# HCM6352_v10.net
KiCad netlist of a schematic drawn in EAGLE
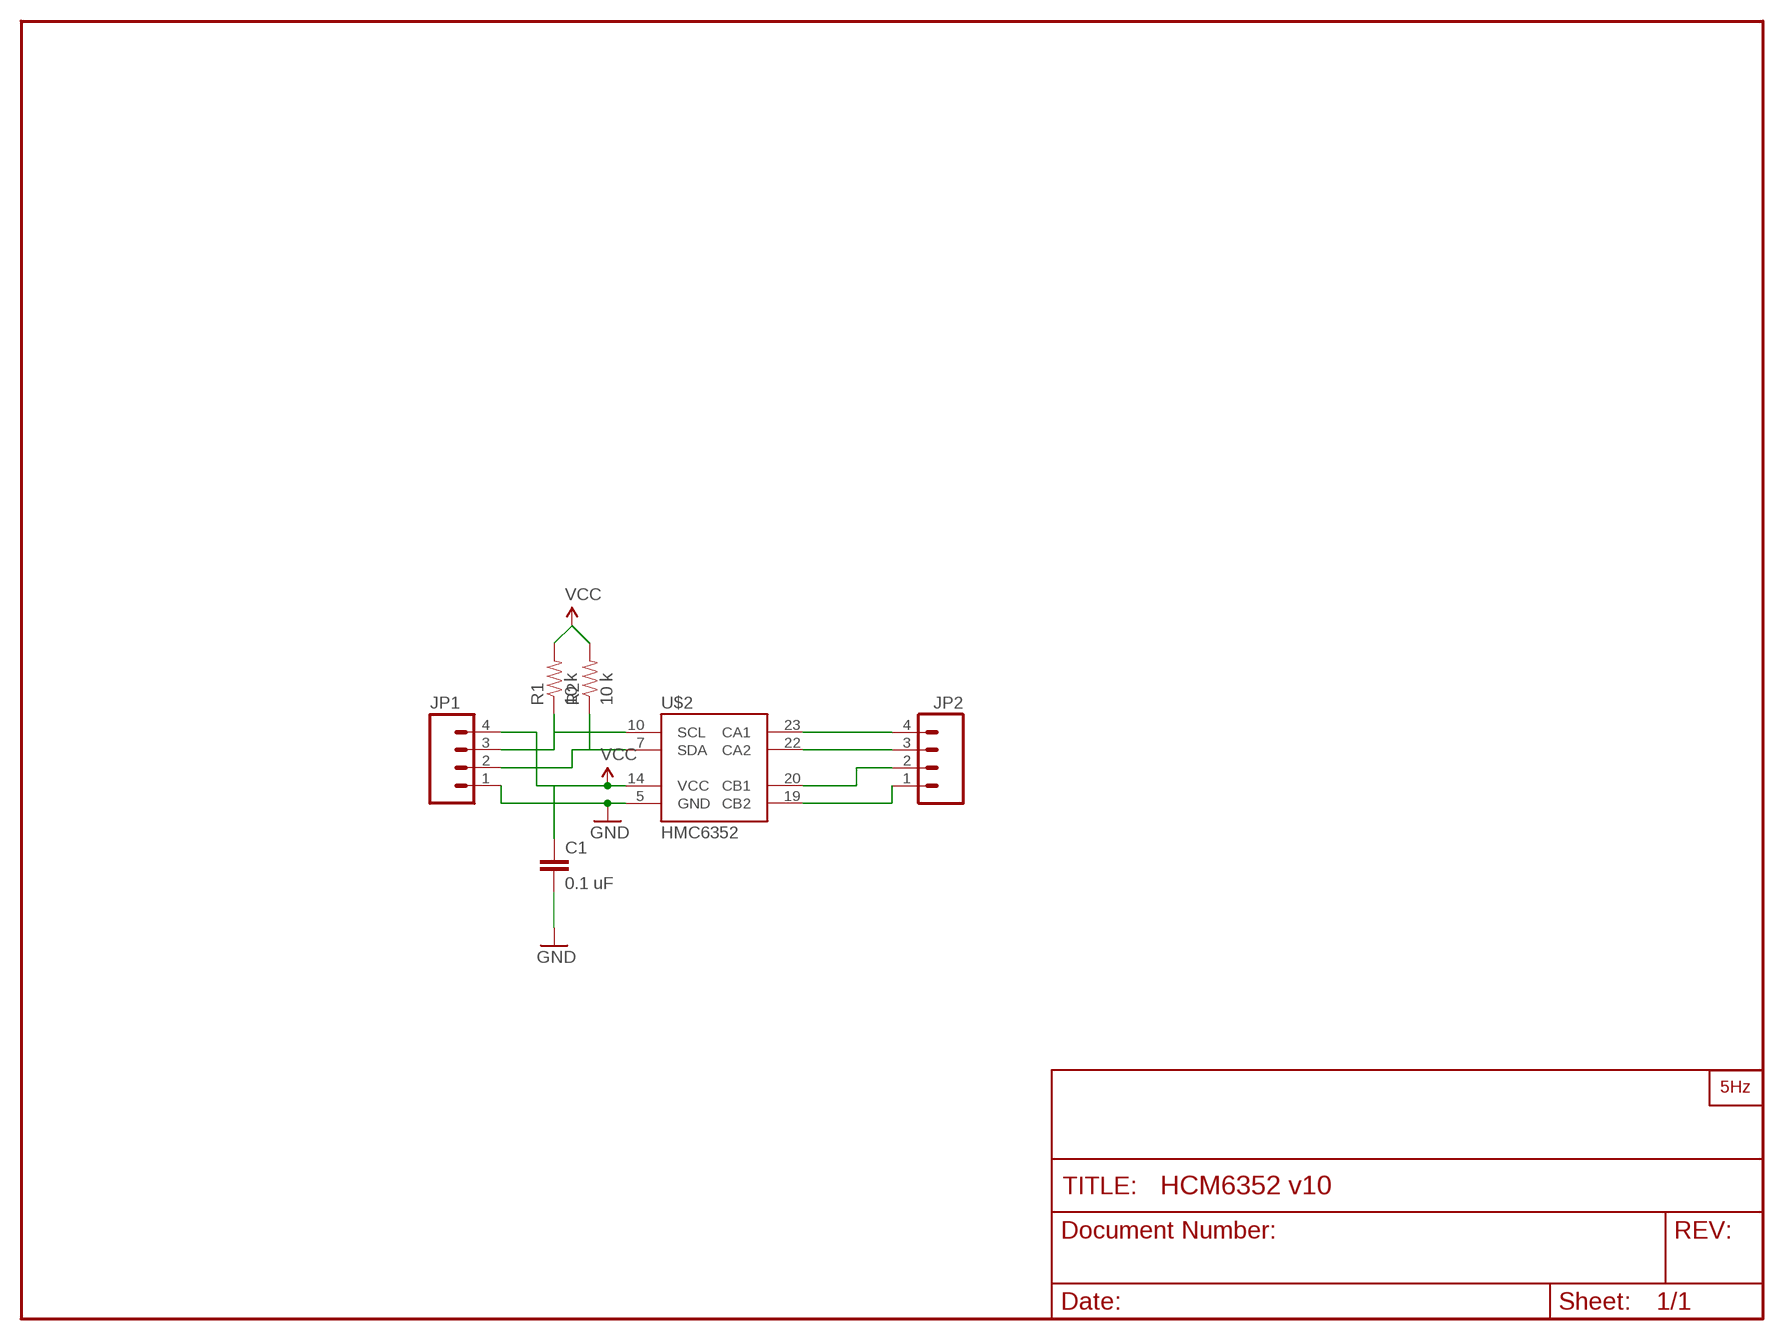
[diagram p0: schematic, sheet 1]

(export (version "E")
  (design (tool "Eeschema 10.0.6"))
  (components
    (comp (ref "C1")
      (value "0.1 uF")
      (footprint "eagle-import:0603-CAP")
      (libsource (lib "eagle-import") (part "CAP0603-CAP"))
    )
    (comp (ref "JP1")
      (value "M04PTH")
      (footprint "eagle-import:1X04")
      (libsource (lib "eagle-import") (part "M04PTH"))
    )
    (comp (ref "JP2")
      (value "M04PTH")
      (footprint "eagle-import:1X04")
      (libsource (lib "eagle-import") (part "M04PTH"))
    )
    (comp (ref "R1")
      (value "10 k")
      (footprint "eagle-import:0603-RES")
      (libsource (lib "eagle-import") (part "RESISTOR0603-RES"))
    )
    (comp (ref "R2")
      (value "10 k")
      (footprint "eagle-import:0603-RES")
      (libsource (lib "eagle-import") (part "RESISTOR0603-RES"))
    )
    (comp (ref "U$1")
      (value "LOGO2_SILK5MM")
      (footprint "eagle-import:LOGO2_5MM")
      (libsource (lib "eagle-import") (part "LOGO2_SILK5MM"))
    )
    (comp (ref "U$2")
      (value "HMC6352")
      (footprint "eagle-import:LCC24")
      (libsource (lib "eagle-import") (part "HMC6352"))
    )
  )
  (nets
    (net (code "1") (name "GND") (class "Default")
      (node (ref "C1") (pin "2") (pinfunction "2_2") (pintype "passive"))
      (node (ref "JP1") (pin "1") (pinfunction "1_1") (pintype "passive"))
      (node (ref "U$2") (pin "5") (pinfunction "GND_5") (pintype "bidirectional"))
    )
    (net (code "2") (name "Net-(U$2-CA1)") (class "Default")
      (node (ref "JP2") (pin "4") (pinfunction "4_4") (pintype "passive"))
      (node (ref "U$2") (pin "23") (pinfunction "CA1_23") (pintype "bidirectional"))
    )
    (net (code "3") (name "Net-(U$2-CA2)") (class "Default")
      (node (ref "JP2") (pin "3") (pinfunction "3_3") (pintype "passive"))
      (node (ref "U$2") (pin "22") (pinfunction "CA2_22") (pintype "bidirectional"))
    )
    (net (code "4") (name "Net-(U$2-CB1)") (class "Default")
      (node (ref "JP2") (pin "2") (pinfunction "2_2") (pintype "passive"))
      (node (ref "U$2") (pin "20") (pinfunction "CB1_20") (pintype "bidirectional"))
    )
    (net (code "5") (name "Net-(U$2-CB2)") (class "Default")
      (node (ref "JP2") (pin "1") (pinfunction "1_1") (pintype "passive"))
      (node (ref "U$2") (pin "19") (pinfunction "CB2_19") (pintype "bidirectional"))
    )
    (net (code "6") (name "Net-(U$2-SCL)") (class "Default")
      (node (ref "JP1") (pin "3") (pinfunction "3_3") (pintype "passive"))
      (node (ref "R1") (pin "1") (pinfunction "1_1") (pintype "passive"))
      (node (ref "U$2") (pin "10") (pinfunction "SCL_10") (pintype "bidirectional"))
    )
    (net (code "7") (name "Net-(U$2-SDA)") (class "Default")
      (node (ref "JP1") (pin "2") (pinfunction "2_2") (pintype "passive"))
      (node (ref "R2") (pin "1") (pinfunction "1_1") (pintype "passive"))
      (node (ref "U$2") (pin "7") (pinfunction "SDA_7") (pintype "bidirectional"))
    )
    (net (code "8") (name "VCC") (class "Default")
      (node (ref "C1") (pin "1") (pinfunction "1_1") (pintype "passive"))
      (node (ref "JP1") (pin "4") (pinfunction "4_4") (pintype "passive"))
      (node (ref "R1") (pin "2") (pinfunction "2_2") (pintype "passive"))
      (node (ref "R2") (pin "2") (pinfunction "2_2") (pintype "passive"))
      (node (ref "U$2") (pin "14") (pinfunction "VCC_14") (pintype "bidirectional"))
    )
  )
)
